# MCU.net
KiCad netlist of a schematic drawn in Altium Designer
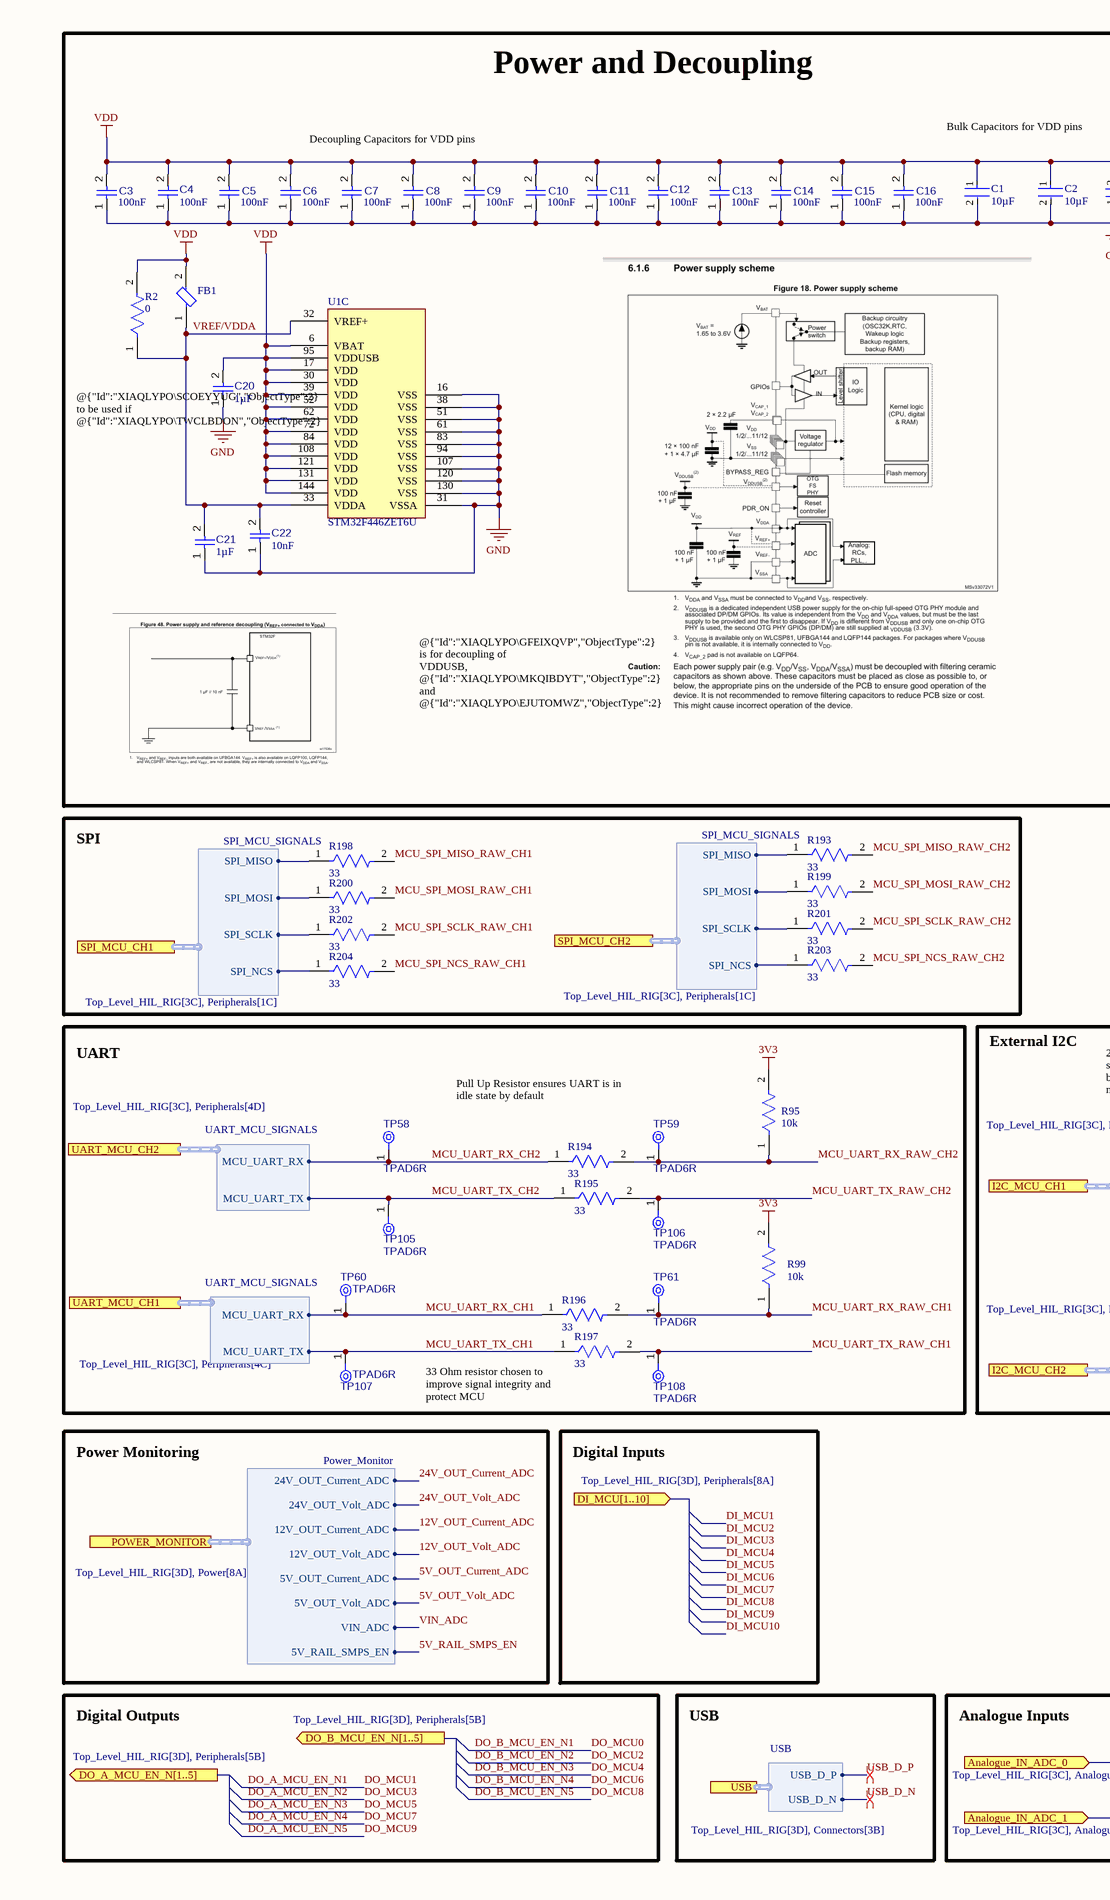
[diagram p0:  MCU.SchDoc, left]
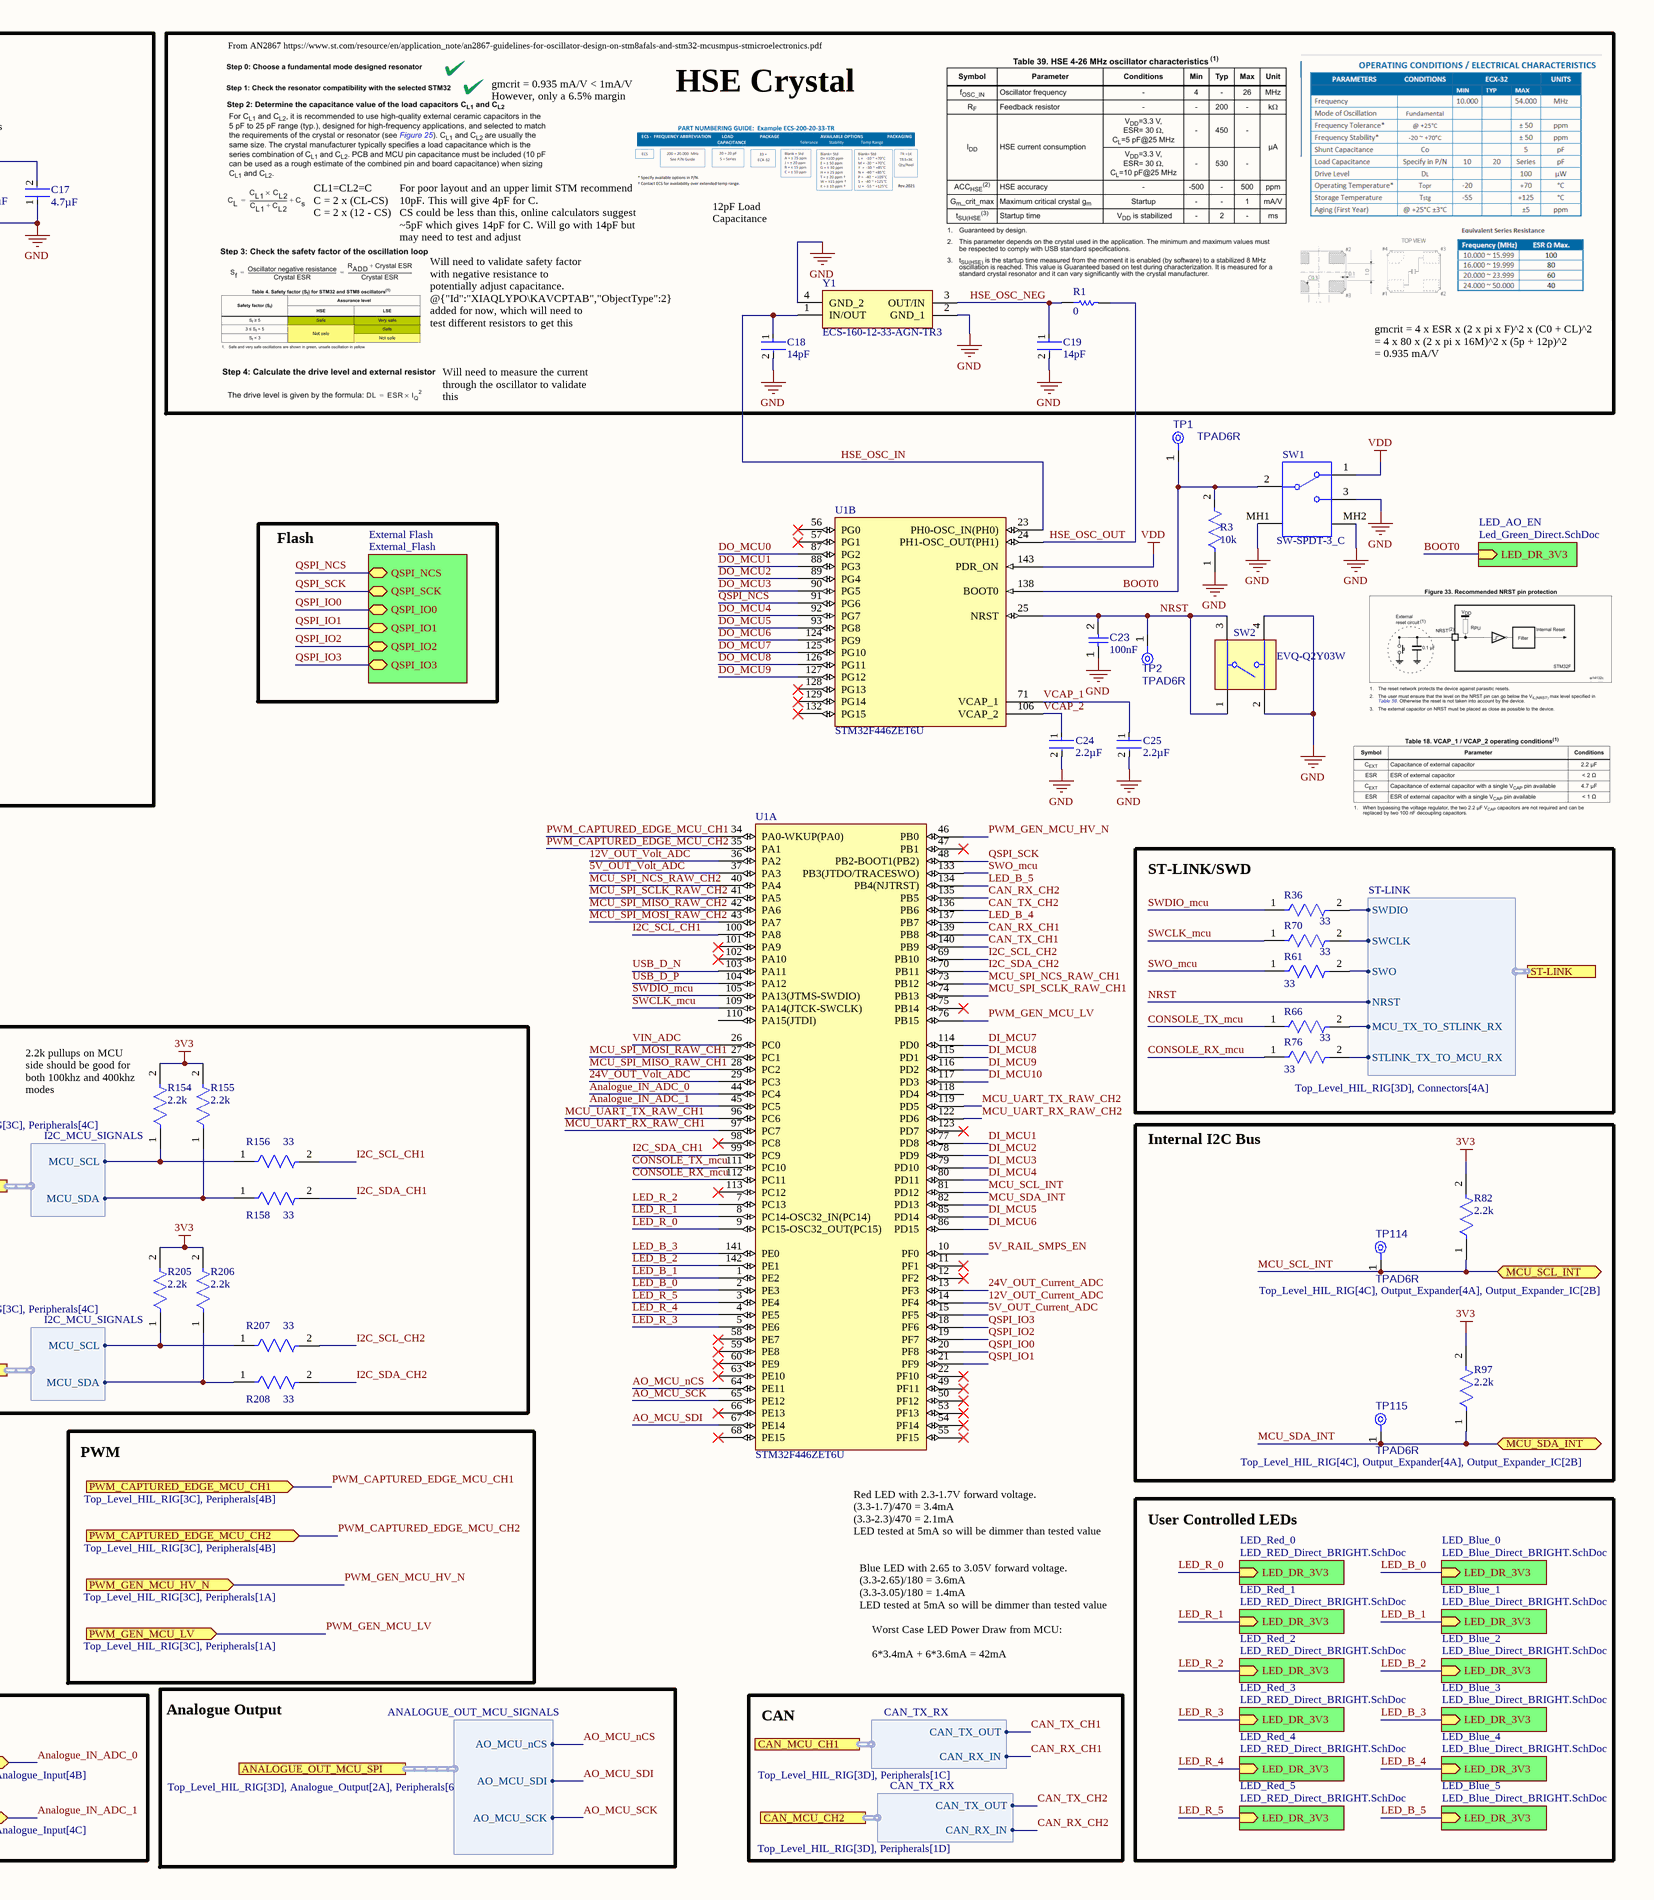
[diagram p1:  MCU.SchDoc, right]

(export (version "E")
  (design (tool "Eeschema 10.0.6"))
  (components
    (comp (ref "C1")
      (value "10µF")
      (footprint "FP-GRM31C-0_2-e0_3_0_8-IPC_C")
      (description "25V 10uF X7R ±10% 1206 Multilayer Ceramic Capacitors MLCC - SMD/SMT ROHS")
      (fields (field (name "TOLERANCE") "10%") (field (name "VOLTAGE") "25V"))
      (libsource (lib "HIL RIG FYP") (part "02cd4be3c70576c341d710602a673aa"))
    )
    (comp (ref "C2")
      (value "10µF")
      (footprint "FP-GRM31C-0_2-e0_3_0_8-IPC_C")
      (description "25V 10uF X7R ±10% 1206 Multilayer Ceramic Capacitors MLCC - SMD/SMT ROHS")
      (fields (field (name "TOLERANCE") "10%") (field (name "VOLTAGE") "25V"))
      (libsource (lib "HIL RIG FYP") (part "02cd4be3c70576c341d710602a673aa"))
    )
    (comp (ref "C3")
      (value "100nF")
      (footprint "CAPC1005X55X25ML05T10")
      (description "10V 100nF X7R ±10% 0402 Multilayer Ceramic Capacitors MLCC - SMD/SMT ROHS")
      (fields (field (name "TOLERANCE") "10%") (field (name "VOLTAGE") "10V"))
      (libsource (lib "HIL RIG FYP") (part "CAP-NP-2"))
    )
    (comp (ref "C4")
      (value "100nF")
      (footprint "CAPC1005X55X25ML05T10")
      (description "10V 100nF X7R ±10% 0402 Multilayer Ceramic Capacitors MLCC - SMD/SMT ROHS")
      (fields (field (name "TOLERANCE") "10%") (field (name "VOLTAGE") "10V"))
      (libsource (lib "HIL RIG FYP") (part "CAP-NP-2"))
    )
    (comp (ref "C5")
      (value "100nF")
      (footprint "CAPC1005X55X25ML05T10")
      (description "10V 100nF X7R ±10% 0402 Multilayer Ceramic Capacitors MLCC - SMD/SMT ROHS")
      (fields (field (name "TOLERANCE") "10%") (field (name "VOLTAGE") "10V"))
      (libsource (lib "HIL RIG FYP") (part "CAP-NP-2"))
    )
    (comp (ref "C6")
      (value "100nF")
      (footprint "CAPC1005X55X25ML05T10")
      (description "10V 100nF X7R ±10% 0402 Multilayer Ceramic Capacitors MLCC - SMD/SMT ROHS")
      (fields (field (name "TOLERANCE") "10%") (field (name "VOLTAGE") "10V"))
      (libsource (lib "HIL RIG FYP") (part "CAP-NP-2"))
    )
    (comp (ref "C7")
      (value "100nF")
      (footprint "CAPC1005X55X25ML05T10")
      (description "10V 100nF X7R ±10% 0402 Multilayer Ceramic Capacitors MLCC - SMD/SMT ROHS")
      (fields (field (name "TOLERANCE") "10%") (field (name "VOLTAGE") "10V"))
      (libsource (lib "HIL RIG FYP") (part "CAP-NP-2"))
    )
    (comp (ref "C8")
      (value "100nF")
      (footprint "CAPC1005X55X25ML05T10")
      (description "10V 100nF X7R ±10% 0402 Multilayer Ceramic Capacitors MLCC - SMD/SMT ROHS")
      (fields (field (name "TOLERANCE") "10%") (field (name "VOLTAGE") "10V"))
      (libsource (lib "HIL RIG FYP") (part "CAP-NP-2"))
    )
    (comp (ref "C9")
      (value "100nF")
      (footprint "CAPC1005X55X25ML05T10")
      (description "10V 100nF X7R ±10% 0402 Multilayer Ceramic Capacitors MLCC - SMD/SMT ROHS")
      (fields (field (name "TOLERANCE") "10%") (field (name "VOLTAGE") "10V"))
      (libsource (lib "HIL RIG FYP") (part "CAP-NP-2"))
    )
    (comp (ref "C10")
      (value "100nF")
      (footprint "CAPC1005X55X25ML05T10")
      (description "10V 100nF X7R ±10% 0402 Multilayer Ceramic Capacitors MLCC - SMD/SMT ROHS")
      (fields (field (name "TOLERANCE") "10%") (field (name "VOLTAGE") "10V"))
      (libsource (lib "HIL RIG FYP") (part "CAP-NP-2"))
    )
    (comp (ref "C11")
      (value "100nF")
      (footprint "CAPC1005X55X25ML05T10")
      (description "10V 100nF X7R ±10% 0402 Multilayer Ceramic Capacitors MLCC - SMD/SMT ROHS")
      (fields (field (name "TOLERANCE") "10%") (field (name "VOLTAGE") "10V"))
      (libsource (lib "HIL RIG FYP") (part "CAP-NP-2"))
    )
    (comp (ref "C12")
      (value "100nF")
      (footprint "CAPC1005X55X25ML05T10")
      (description "10V 100nF X7R ±10% 0402 Multilayer Ceramic Capacitors MLCC - SMD/SMT ROHS")
      (fields (field (name "TOLERANCE") "10%") (field (name "VOLTAGE") "10V"))
      (libsource (lib "HIL RIG FYP") (part "CAP-NP-2"))
    )
    (comp (ref "C13")
      (value "100nF")
      (footprint "CAPC1005X55X25ML05T10")
      (description "10V 100nF X7R ±10% 0402 Multilayer Ceramic Capacitors MLCC - SMD/SMT ROHS")
      (fields (field (name "TOLERANCE") "10%") (field (name "VOLTAGE") "10V"))
      (libsource (lib "HIL RIG FYP") (part "CAP-NP-2"))
    )
    (comp (ref "C14")
      (value "100nF")
      (footprint "CAPC1005X55X25ML05T10")
      (description "10V 100nF X7R ±10% 0402 Multilayer Ceramic Capacitors MLCC - SMD/SMT ROHS")
      (fields (field (name "TOLERANCE") "10%") (field (name "VOLTAGE") "10V"))
      (libsource (lib "HIL RIG FYP") (part "CAP-NP-2"))
    )
    (comp (ref "C15")
      (value "100nF")
      (footprint "CAPC1005X55X25ML05T10")
      (description "10V 100nF X7R ±10% 0402 Multilayer Ceramic Capacitors MLCC - SMD/SMT ROHS")
      (fields (field (name "TOLERANCE") "10%") (field (name "VOLTAGE") "10V"))
      (libsource (lib "HIL RIG FYP") (part "CAP-NP-2"))
    )
    (comp (ref "C16")
      (value "100nF")
      (footprint "CAPC1005X55X25ML05T10")
      (description "10V 100nF X7R ±10% 0402 Multilayer Ceramic Capacitors MLCC - SMD/SMT ROHS")
      (fields (field (name "TOLERANCE") "10%") (field (name "VOLTAGE") "10V"))
      (libsource (lib "HIL RIG FYP") (part "CAP-NP-2"))
    )
    (comp (ref "C17")
      (value "4.7µF")
      (footprint "FP-GRM21B-0_2-e0_2_0_7-MFG")
      (description "50V 4.7uF X7R ±10% 0805 Multilayer Ceramic Capacitors MLCC - SMD/SMT ROHS")
      (fields (field (name "TOLERANCE") "10%") (field (name "Comment") "GRM21BZ71H475KE15L"))
      (libsource (lib "HIL RIG FYP") (part "b4654b650e69147ec39a6b967a45e02"))
    )
    (comp (ref "C18")
      (value "14pF")
      (footprint "FP-GJM155-0_05-IPC_A")
      (description "GJM Series 0402 14 pF 50 V ±1 % Tolerance C0G SMT Monolithic Ceramic Capacitor")
      (fields (field (name "TOLERANCE") "1%") (field (name "Comment") "GJM1555C1H140FB01D"))
      (libsource (lib "HIL RIG FYP") (part "02cd4be3c70576c341d710602a673aa"))
    )
    (comp (ref "C19")
      (value "14pF")
      (footprint "FP-GJM155-0_05-IPC_A")
      (description "GJM Series 0402 14 pF 50 V ±1 % Tolerance C0G SMT Monolithic Ceramic Capacitor")
      (fields (field (name "TOLERANCE") "1%") (field (name "Comment") "GJM1555C1H140FB01D"))
      (libsource (lib "HIL RIG FYP") (part "02cd4be3c70576c341d710602a673aa"))
    )
    (comp (ref "C20")
      (value "1µF")
      (footprint "CAPC1608X90X40LL10T20")
      (description "Chip Capacitor, 1 uF, +/- 10%, 25 V, 0603 (1608 Metric)")
      (fields (field (name "TOLERANCE") "10%") (field (name "Comment") "Capacitor 1 uF +/- 10% 25 V 0603"))
      (libsource (lib "HIL RIG FYP") (part "CAP-NP-2"))
    )
    (comp (ref "C21")
      (value "1µF")
      (footprint "CAPC1608X90X40LL10T20")
      (description "Chip Capacitor, 1 uF, +/- 10%, 25 V, 0603 (1608 Metric)")
      (fields (field (name "TOLERANCE") "10%") (field (name "Comment") "Capacitor 1 uF +/- 10% 25 V 0603"))
      (libsource (lib "HIL RIG FYP") (part "CAP-NP-2"))
    )
    (comp (ref "C22")
      (value "10nF")
      (footprint "CAPC0402(1005)60_L")
      (description "Chip Capacitor, 10nF +/-20%, 50V, 0402, Thickness 0.6 mm")
      (fields (field (name "TOLERANCE") "5%") (field (name "Comment") "Capacitor 10nF +/-20% 50V 0402"))
      (libsource (lib "HIL RIG FYP") (part "CAP-NP-2"))
    )
    (comp (ref "C23")
      (value "100nF")
      (footprint "CAPC1005X55X25ML05T10")
      (description "10V 100nF X7R ±10% 0402 Multilayer Ceramic Capacitors MLCC - SMD/SMT ROHS")
      (fields (field (name "TOLERANCE") "10%") (field (name "VOLTAGE") "10V"))
      (libsource (lib "HIL RIG FYP") (part "CAP-NP-2"))
    )
    (comp (ref "C24")
      (value "2.2µF")
      (footprint "FP-CC0402-IPC_A")
      (description "10V 2.2uF X5R ±10% 0402 Multilayer Ceramic Capacitors MLCC - SMD/SMT ROHS")
      (fields (field (name "TOLERANCE") "10%") (field (name "Comment") "CC0402KRX5R6BB225"))
      (libsource (lib "HIL RIG FYP") (part "11868f565c42a9108669ba33697ecf6"))
    )
    (comp (ref "C25")
      (value "2.2µF")
      (footprint "FP-CC0402-IPC_A")
      (description "10V 2.2uF X5R ±10% 0402 Multilayer Ceramic Capacitors MLCC - SMD/SMT ROHS")
      (fields (field (name "TOLERANCE") "10%") (field (name "Comment") "CC0402KRX5R6BB225"))
      (libsource (lib "HIL RIG FYP") (part "11868f565c42a9108669ba33697ecf6"))
    )
    (comp (ref "FB1")
      (value "BLM15AG121SH1D")
      (footprint "FP-BLM15-0_05-IPC_A")
      (description "Ferrite Beads Multi-Layer 120Ohm 25% 100MHz 500mA 250mOhm DCR 0402 Paper T/R")
      (fields (field (name "TOLERANCE") "25%"))
      (libsource (lib "HIL RIG FYP") (part "5f30dd21d616792df468990f7003faa"))
    )
    (comp (ref "R1")
      (value "0")
      (footprint "RESC1608X55X25ML10T15")
      (description "Chip Resistor, 0 Ohm, 0.1 W, -55 to 155 degC, 0603 (1608 Metric)")
      (fields (field (name "POWER") "100mW") (field (name "TOLERANCE") "5%"))
      (libsource (lib "HIL RIG FYP") (part "RES-2"))
    )
    (comp (ref "R2")
      (value "0")
      (footprint "FP-MCS0402-IPC_B")
      (description "Zero Ohm Resistor, Jumper, 0402 [1005 Metric], Thin Film, 100 mW, 630 mA, Surface Mount Device")
      (fields (field (name "Comment") "MCS04020Z0000ZE000"))
      (libsource (lib "HIL RIG FYP") (part "1029c3af85768c4190bb7ad29bc67b5"))
    )
    (comp (ref "R3")
      (value "10k")
      (footprint "FP-RT0603-IPC_C")
      (description "Res Thin Film 0603 10K Ohm 0.1% 1/10W ¦25ppm/¦C SMD Paper T/R")
      (fields (field (name "TOLERANCE") "0.1%") (field (name "Comment") "RT0603BRD0710KL"))
      (libsource (lib "HIL RIG FYP") (part "1029c3af85768c4190bb7ad29bc67b5"))
    )
    (comp (ref "R36")
      (value "33")
      (footprint "FP-AC0603-IPC_C")
      (description "Res Thick Film 0603 33 Ohm 1% 0.1W(1/10W) ±100ppm/C Pad SMD T/R Automotive AEC-Q200")
      (fields (field (name "TOLERANCE") "1%") (field (name "Comment") "AC0603FR-0733RL"))
      (libsource (lib "HIL RIG FYP") (part "1029c3af85768c4190bb7ad29bc67b5"))
    )
    (comp (ref "R61")
      (value "33")
      (footprint "FP-AC0603-IPC_C")
      (description "Res Thick Film 0603 33 Ohm 1% 0.1W(1/10W) ±100ppm/C Pad SMD T/R Automotive AEC-Q200")
      (fields (field (name "TOLERANCE") "1%") (field (name "Comment") "AC0603FR-0733RL"))
      (libsource (lib "HIL RIG FYP") (part "1029c3af85768c4190bb7ad29bc67b5"))
    )
    (comp (ref "R66")
      (value "33")
      (footprint "FP-AC0603-IPC_C")
      (description "Res Thick Film 0603 33 Ohm 1% 0.1W(1/10W) ±100ppm/C Pad SMD T/R Automotive AEC-Q200")
      (fields (field (name "TOLERANCE") "1%") (field (name "Comment") "AC0603FR-0733RL"))
      (libsource (lib "HIL RIG FYP") (part "1029c3af85768c4190bb7ad29bc67b5"))
    )
    (comp (ref "R70")
      (value "33")
      (footprint "FP-AC0603-IPC_C")
      (description "Res Thick Film 0603 33 Ohm 1% 0.1W(1/10W) ±100ppm/C Pad SMD T/R Automotive AEC-Q200")
      (fields (field (name "TOLERANCE") "1%") (field (name "Comment") "AC0603FR-0733RL"))
      (libsource (lib "HIL RIG FYP") (part "1029c3af85768c4190bb7ad29bc67b5"))
    )
    (comp (ref "R76")
      (value "33")
      (footprint "FP-AC0603-IPC_C")
      (description "Res Thick Film 0603 33 Ohm 1% 0.1W(1/10W) ±100ppm/C Pad SMD T/R Automotive AEC-Q200")
      (fields (field (name "TOLERANCE") "1%") (field (name "Comment") "AC0603FR-0733RL"))
      (libsource (lib "HIL RIG FYP") (part "1029c3af85768c4190bb7ad29bc67b5"))
    )
    (comp (ref "R82")
      (value "2.2k")
      (footprint "FP-RT0603-IPC_C")
      (description "100mW Thin Film Resistor 75V ±25ppm/℃ ±0.1% 2.2kΩ 0603 Chip Resistor - Surface Mount ROHS")
      (fields (field (name "TOLERANCE") "0.1%") (field (name "Comment") "RT0603BRD072K2L"))
      (libsource (lib "HIL RIG FYP") (part "1029c3af85768c4190bb7ad29bc67b5"))
    )
    (comp (ref "R95")
      (value "10k")
      (footprint "FP-RT0603-IPC_C")
      (description "Res Thin Film 0603 10K Ohm 0.1% 1/10W ¦25ppm/¦C SMD Paper T/R")
      (fields (field (name "TOLERANCE") "0.1%") (field (name "Comment") "RT0603BRD0710KL"))
      (libsource (lib "HIL RIG FYP") (part "1029c3af85768c4190bb7ad29bc67b5"))
    )
    (comp (ref "R97")
      (value "2.2k")
      (footprint "FP-RT0603-IPC_C")
      (description "100mW Thin Film Resistor 75V ±25ppm/℃ ±0.1% 2.2kΩ 0603 Chip Resistor - Surface Mount ROHS")
      (fields (field (name "TOLERANCE") "0.1%") (field (name "Comment") "RT0603BRD072K2L"))
      (libsource (lib "HIL RIG FYP") (part "1029c3af85768c4190bb7ad29bc67b5"))
    )
    (comp (ref "R99")
      (value "10k")
      (footprint "FP-RT0603-IPC_C")
      (description "Res Thin Film 0603 10K Ohm 0.1% 1/10W ¦25ppm/¦C SMD Paper T/R")
      (fields (field (name "TOLERANCE") "0.1%") (field (name "Comment") "RT0603BRD0710KL"))
      (libsource (lib "HIL RIG FYP") (part "1029c3af85768c4190bb7ad29bc67b5"))
    )
    (comp (ref "R154")
      (value "2.2k")
      (footprint "FP-RT0603-IPC_C")
      (description "100mW Thin Film Resistor 75V ±25ppm/℃ ±0.1% 2.2kΩ 0603 Chip Resistor - Surface Mount ROHS")
      (fields (field (name "TOLERANCE") "0.1%") (field (name "Comment") "RT0603BRD072K2L"))
      (libsource (lib "HIL RIG FYP") (part "1029c3af85768c4190bb7ad29bc67b5"))
    )
    (comp (ref "R155")
      (value "2.2k")
      (footprint "FP-RT0603-IPC_C")
      (description "100mW Thin Film Resistor 75V ±25ppm/℃ ±0.1% 2.2kΩ 0603 Chip Resistor - Surface Mount ROHS")
      (fields (field (name "TOLERANCE") "0.1%") (field (name "Comment") "RT0603BRD072K2L"))
      (libsource (lib "HIL RIG FYP") (part "1029c3af85768c4190bb7ad29bc67b5"))
    )
    (comp (ref "R156")
      (value "33")
      (footprint "FP-AC0603-IPC_C")
      (description "Res Thick Film 0603 33 Ohm 1% 0.1W(1/10W) ±100ppm/C Pad SMD T/R Automotive AEC-Q200")
      (fields (field (name "TOLERANCE") "1%") (field (name "Comment") "AC0603FR-0733RL"))
      (libsource (lib "HIL RIG FYP") (part "1029c3af85768c4190bb7ad29bc67b5"))
    )
    (comp (ref "R158")
      (value "33")
      (footprint "FP-AC0603-IPC_C")
      (description "Res Thick Film 0603 33 Ohm 1% 0.1W(1/10W) ±100ppm/C Pad SMD T/R Automotive AEC-Q200")
      (fields (field (name "TOLERANCE") "1%") (field (name "Comment") "AC0603FR-0733RL"))
      (libsource (lib "HIL RIG FYP") (part "1029c3af85768c4190bb7ad29bc67b5"))
    )
    (comp (ref "R193")
      (value "33")
      (footprint "FP-AC0603-IPC_C")
      (description "Res Thick Film 0603 33 Ohm 1% 0.1W(1/10W) ±100ppm/C Pad SMD T/R Automotive AEC-Q200")
      (fields (field (name "TOLERANCE") "1%") (field (name "Comment") "AC0603FR-0733RL"))
      (libsource (lib "HIL RIG FYP") (part "1029c3af85768c4190bb7ad29bc67b5"))
    )
    (comp (ref "R194")
      (value "33")
      (footprint "FP-AC0603-IPC_C")
      (description "Res Thick Film 0603 33 Ohm 1% 0.1W(1/10W) ±100ppm/C Pad SMD T/R Automotive AEC-Q200")
      (fields (field (name "TOLERANCE") "1%") (field (name "Comment") "AC0603FR-0733RL"))
      (libsource (lib "HIL RIG FYP") (part "1029c3af85768c4190bb7ad29bc67b5"))
    )
    (comp (ref "R195")
      (value "33")
      (footprint "FP-AC0603-IPC_C")
      (description "Res Thick Film 0603 33 Ohm 1% 0.1W(1/10W) ±100ppm/C Pad SMD T/R Automotive AEC-Q200")
      (fields (field (name "TOLERANCE") "1%") (field (name "Comment") "AC0603FR-0733RL"))
      (libsource (lib "HIL RIG FYP") (part "1029c3af85768c4190bb7ad29bc67b5"))
    )
    (comp (ref "R196")
      (value "33")
      (footprint "FP-AC0603-IPC_C")
      (description "Res Thick Film 0603 33 Ohm 1% 0.1W(1/10W) ±100ppm/C Pad SMD T/R Automotive AEC-Q200")
      (fields (field (name "TOLERANCE") "1%") (field (name "Comment") "AC0603FR-0733RL"))
      (libsource (lib "HIL RIG FYP") (part "1029c3af85768c4190bb7ad29bc67b5"))
    )
    (comp (ref "R197")
      (value "33")
      (footprint "FP-AC0603-IPC_C")
      (description "Res Thick Film 0603 33 Ohm 1% 0.1W(1/10W) ±100ppm/C Pad SMD T/R Automotive AEC-Q200")
      (fields (field (name "TOLERANCE") "1%") (field (name "Comment") "AC0603FR-0733RL"))
      (libsource (lib "HIL RIG FYP") (part "1029c3af85768c4190bb7ad29bc67b5"))
    )
    (comp (ref "R198")
      (value "33")
      (footprint "FP-AC0603-IPC_C")
      (description "Res Thick Film 0603 33 Ohm 1% 0.1W(1/10W) ±100ppm/C Pad SMD T/R Automotive AEC-Q200")
      (fields (field (name "TOLERANCE") "1%") (field (name "Comment") "AC0603FR-0733RL"))
      (libsource (lib "HIL RIG FYP") (part "1029c3af85768c4190bb7ad29bc67b5"))
    )
    (comp (ref "R199")
      (value "33")
      (footprint "FP-AC0603-IPC_C")
      (description "Res Thick Film 0603 33 Ohm 1% 0.1W(1/10W) ±100ppm/C Pad SMD T/R Automotive AEC-Q200")
      (fields (field (name "TOLERANCE") "1%") (field (name "Comment") "AC0603FR-0733RL"))
      (libsource (lib "HIL RIG FYP") (part "1029c3af85768c4190bb7ad29bc67b5"))
    )
    (comp (ref "R200")
      (value "33")
      (footprint "FP-AC0603-IPC_C")
      (description "Res Thick Film 0603 33 Ohm 1% 0.1W(1/10W) ±100ppm/C Pad SMD T/R Automotive AEC-Q200")
      (fields (field (name "TOLERANCE") "1%") (field (name "Comment") "AC0603FR-0733RL"))
      (libsource (lib "HIL RIG FYP") (part "1029c3af85768c4190bb7ad29bc67b5"))
    )
    (comp (ref "R201")
      (value "33")
      (footprint "FP-AC0603-IPC_C")
      (description "Res Thick Film 0603 33 Ohm 1% 0.1W(1/10W) ±100ppm/C Pad SMD T/R Automotive AEC-Q200")
      (fields (field (name "TOLERANCE") "1%") (field (name "Comment") "AC0603FR-0733RL"))
      (libsource (lib "HIL RIG FYP") (part "1029c3af85768c4190bb7ad29bc67b5"))
    )
    (comp (ref "R202")
      (value "33")
      (footprint "FP-AC0603-IPC_C")
      (description "Res Thick Film 0603 33 Ohm 1% 0.1W(1/10W) ±100ppm/C Pad SMD T/R Automotive AEC-Q200")
      (fields (field (name "TOLERANCE") "1%") (field (name "Comment") "AC0603FR-0733RL"))
      (libsource (lib "HIL RIG FYP") (part "1029c3af85768c4190bb7ad29bc67b5"))
    )
    (comp (ref "R203")
      (value "33")
      (footprint "FP-AC0603-IPC_C")
      (description "Res Thick Film 0603 33 Ohm 1% 0.1W(1/10W) ±100ppm/C Pad SMD T/R Automotive AEC-Q200")
      (fields (field (name "TOLERANCE") "1%") (field (name "Comment") "AC0603FR-0733RL"))
      (libsource (lib "HIL RIG FYP") (part "1029c3af85768c4190bb7ad29bc67b5"))
    )
    (comp (ref "R204")
      (value "33")
      (footprint "FP-AC0603-IPC_C")
      (description "Res Thick Film 0603 33 Ohm 1% 0.1W(1/10W) ±100ppm/C Pad SMD T/R Automotive AEC-Q200")
      (fields (field (name "TOLERANCE") "1%") (field (name "Comment") "AC0603FR-0733RL"))
      (libsource (lib "HIL RIG FYP") (part "1029c3af85768c4190bb7ad29bc67b5"))
    )
    (comp (ref "R205")
      (value "2.2k")
      (footprint "FP-RT0603-IPC_C")
      (description "100mW Thin Film Resistor 75V ±25ppm/℃ ±0.1% 2.2kΩ 0603 Chip Resistor - Surface Mount ROHS")
      (fields (field (name "TOLERANCE") "0.1%") (field (name "Comment") "RT0603BRD072K2L"))
      (libsource (lib "HIL RIG FYP") (part "1029c3af85768c4190bb7ad29bc67b5"))
    )
    (comp (ref "R206")
      (value "2.2k")
      (footprint "FP-RT0603-IPC_C")
      (description "100mW Thin Film Resistor 75V ±25ppm/℃ ±0.1% 2.2kΩ 0603 Chip Resistor - Surface Mount ROHS")
      (fields (field (name "TOLERANCE") "0.1%") (field (name "Comment") "RT0603BRD072K2L"))
      (libsource (lib "HIL RIG FYP") (part "1029c3af85768c4190bb7ad29bc67b5"))
    )
    (comp (ref "R207")
      (value "33")
      (footprint "FP-AC0603-IPC_C")
      (description "Res Thick Film 0603 33 Ohm 1% 0.1W(1/10W) ±100ppm/C Pad SMD T/R Automotive AEC-Q200")
      (fields (field (name "TOLERANCE") "1%") (field (name "Comment") "AC0603FR-0733RL"))
      (libsource (lib "HIL RIG FYP") (part "1029c3af85768c4190bb7ad29bc67b5"))
    )
    (comp (ref "R208")
      (value "33")
      (footprint "FP-AC0603-IPC_C")
      (description "Res Thick Film 0603 33 Ohm 1% 0.1W(1/10W) ±100ppm/C Pad SMD T/R Automotive AEC-Q200")
      (fields (field (name "TOLERANCE") "1%") (field (name "Comment") "AC0603FR-0733RL"))
      (libsource (lib "HIL RIG FYP") (part "1029c3af85768c4190bb7ad29bc67b5"))
    )
    (comp (ref "SW1")
      (value "SW-SPDT-3_C")
      (footprint "SS12F44G5")
      (description "Toggle Switches Plugin RoHS")
      (fields (field (name "MANUFACTURER_PART_NUMBER") "SS-12F44-G5"))
      (libsource (lib "HIL RIG FYP") (part "SW-SPDT-3_C"))
    )
    (comp (ref "SW2")
      (value "EVQ-Q2Y03W")
      (footprint "PNSC-EVQQ2_V")
      (description "Switch Tactile ON OFF SPST Round Button J-Bend 0.02A 15VDC 3.5N SMD Embossed T/R")
      (libsource (lib "HIL RIG FYP") (part "SW-SPST-4"))
    )
    (comp (ref "TP1")
      (value "TPAD6R")
      (footprint "TP06R")
      (description "0.6mm round")
      (libsource (lib "HIL RIG FYP") (part "CMP-001-0001-4"))
    )
    (comp (ref "TP2")
      (value "TPAD6R")
      (footprint "TP06R")
      (description "0.6mm round")
      (libsource (lib "HIL RIG FYP") (part "CMP-001-0001-4"))
    )
    (comp (ref "TP58")
      (value "TPAD6R")
      (footprint "TP06R")
      (description "0.6mm round")
      (libsource (lib "HIL RIG FYP") (part "CMP-001-0001-4"))
    )
    (comp (ref "TP59")
      (value "TPAD6R")
      (footprint "TP06R")
      (description "0.6mm round")
      (libsource (lib "HIL RIG FYP") (part "CMP-001-0001-4"))
    )
    (comp (ref "TP60")
      (value "TPAD6R")
      (footprint "TP06R")
      (description "0.6mm round")
      (libsource (lib "HIL RIG FYP") (part "CMP-001-0001-4"))
    )
    (comp (ref "TP61")
      (value "TPAD6R")
      (footprint "TP06R")
      (description "0.6mm round")
      (libsource (lib "HIL RIG FYP") (part "CMP-001-0001-4"))
    )
    (comp (ref "TP105")
      (value "TPAD6R")
      (footprint "TP06R")
      (description "0.6mm round")
      (libsource (lib "HIL RIG FYP") (part "CMP-001-0001-4"))
    )
    (comp (ref "TP106")
      (value "TPAD6R")
      (footprint "TP06R")
      (description "0.6mm round")
      (libsource (lib "HIL RIG FYP") (part "CMP-001-0001-4"))
    )
    (comp (ref "TP107")
      (value "TPAD6R")
      (footprint "TP06R")
      (description "0.6mm round")
      (libsource (lib "HIL RIG FYP") (part "CMP-001-0001-4"))
    )
    (comp (ref "TP108")
      (value "TPAD6R")
      (footprint "TP06R")
      (description "0.6mm round")
      (libsource (lib "HIL RIG FYP") (part "CMP-001-0001-4"))
    )
    (comp (ref "TP114")
      (value "TPAD6R")
      (footprint "TP06R")
      (description "0.6mm round")
      (libsource (lib "HIL RIG FYP") (part "CMP-001-0001-4"))
    )
    (comp (ref "TP115")
      (value "TPAD6R")
      (footprint "TP06R")
      (description "0.6mm round")
      (libsource (lib "HIL RIG FYP") (part "CMP-001-0001-4"))
    )
    (comp (ref "U1")
      (value "STM32F446ZET6U")
      (footprint "STM-LQFP144_N")
      (description "Mcu, 32 Bit, CORTEX-M4, 180MHZ, LQFP-144")
      (libsource (lib "HIL RIG FYP") (part "MC-ARM-STM32F446-LQFP144"))
    )
    (comp (ref "Y1")
      (value "ECS-160-12-33-AGN-TR3")
      (footprint "ECS1601233AGNTR3")
      (description "Crystal or Oscillator")
      (fields (field (name "MOUSER PART NUMBER") "520-160-12-33AGN-TR3"))
      (libsource (lib "HIL RIG FYP") (part "ECS-160-12-33-AGN-TR3"))
    )
  )
  (nets
    (net (code "9") (name "/5V_OUT_Current_ADC") (class "Default")
      (node (ref "U1") (pin "15") (pinfunction "PF5_15") (pintype "bidirectional"))
    )
    (net (code "10") (name "/5V_OUT_Volt_ADC") (class "Default")
      (node (ref "U1") (pin "37") (pinfunction "PA3_37") (pintype "bidirectional"))
    )
    (net (code "11") (name "/5V_RAIL_SMPS_EN") (class "Default")
      (node (ref "U1") (pin "10") (pinfunction "PF0_10") (pintype "bidirectional"))
    )
    (net (code "12") (name "/12V_OUT_Current_ADC") (class "Default")
      (node (ref "U1") (pin "14") (pinfunction "PF4_14") (pintype "bidirectional"))
    )
    (net (code "13") (name "/12V_OUT_Volt_ADC") (class "Default")
      (node (ref "U1") (pin "36") (pinfunction "PA2_36") (pintype "bidirectional"))
    )
    (net (code "14") (name "/24V_OUT_Current_ADC") (class "Default")
      (node (ref "U1") (pin "13") (pinfunction "PF3_13") (pintype "bidirectional"))
    )
    (net (code "15") (name "/24V_OUT_Volt_ADC") (class "Default")
      (node (ref "U1") (pin "29") (pinfunction "PC3_29") (pintype "bidirectional"))
    )
    (net (code "16") (name "/AO_MCU_SCK") (class "Default")
      (node (ref "U1") (pin "65") (pinfunction "PE12_65") (pintype "bidirectional"))
    )
    (net (code "17") (name "/AO_MCU_SDI") (class "Default")
      (node (ref "U1") (pin "67") (pinfunction "PE14_67") (pintype "bidirectional"))
    )
    (net (code "18") (name "/AO_MCU_nCS") (class "Default")
      (node (ref "U1") (pin "64") (pinfunction "PE11_64") (pintype "bidirectional"))
    )
    (net (code "19") (name "/Analogue_IN_ADC_0") (class "Default")
      (node (ref "U1") (pin "44") (pinfunction "PC4_44") (pintype "bidirectional"))
    )
    (net (code "20") (name "/Analogue_IN_ADC_1") (class "Default")
      (node (ref "U1") (pin "45") (pinfunction "PC5_45") (pintype "bidirectional"))
    )
    (net (code "21") (name "/BOOT0") (class "Default")
      (node (ref "R3") (pin "2") (pinfunction "2_2") (pintype "passive"))
      (node (ref "SW1") (pin "2") (pinfunction "2_2") (pintype "passive"))
      (node (ref "TP1") (pin "1") (pinfunction "TP_1") (pintype "passive"))
      (node (ref "U1") (pin "138") (pinfunction "BOOT0_138") (pintype "input"))
    )
    (net (code "22") (name "/CAN_RX_CH1") (class "Default")
      (node (ref "U1") (pin "139") (pinfunction "PB8_139") (pintype "bidirectional"))
    )
    (net (code "23") (name "/CAN_RX_CH2") (class "Default")
      (node (ref "U1") (pin "135") (pinfunction "PB5_135") (pintype "bidirectional"))
    )
    (net (code "24") (name "/CAN_TX_CH1") (class "Default")
      (node (ref "U1") (pin "140") (pinfunction "PB9_140") (pintype "bidirectional"))
    )
    (net (code "25") (name "/CAN_TX_CH2") (class "Default")
      (node (ref "U1") (pin "136") (pinfunction "PB6_136") (pintype "bidirectional"))
    )
    (net (code "26") (name "/CONSOLE_RX_mcu") (class "Default")
      (node (ref "R76") (pin "1") (pinfunction "1_1") (pintype "passive"))
      (node (ref "U1") (pin "112") (pinfunction "PC11_112") (pintype "bidirectional"))
    )
    (net (code "27") (name "/CONSOLE_TX_mcu") (class "Default")
      (node (ref "R66") (pin "1") (pinfunction "1_1") (pintype "passive"))
      (node (ref "U1") (pin "111") (pinfunction "PC10_111") (pintype "bidirectional"))
    )
    (net (code "28") (name "/DI_MCU1") (class "Default")
      (node (ref "U1") (pin "77") (pinfunction "PD8_77") (pintype "bidirectional"))
    )
    (net (code "29") (name "/DI_MCU2") (class "Default")
      (node (ref "U1") (pin "78") (pinfunction "PD9_78") (pintype "bidirectional"))
    )
    (net (code "30") (name "/DI_MCU3") (class "Default")
      (node (ref "U1") (pin "79") (pinfunction "PD10_79") (pintype "bidirectional"))
    )
    (net (code "31") (name "/DI_MCU4") (class "Default")
      (node (ref "U1") (pin "80") (pinfunction "PD11_80") (pintype "bidirectional"))
    )
    (net (code "32") (name "/DI_MCU5") (class "Default")
      (node (ref "U1") (pin "85") (pinfunction "PD14_85") (pintype "bidirectional"))
    )
    (net (code "33") (name "/DI_MCU6") (class "Default")
      (node (ref "U1") (pin "86") (pinfunction "PD15_86") (pintype "bidirectional"))
    )
    (net (code "34") (name "/DI_MCU7") (class "Default")
      (node (ref "U1") (pin "114") (pinfunction "PD0_114") (pintype "bidirectional"))
    )
    (net (code "35") (name "/DI_MCU8") (class "Default")
      (node (ref "U1") (pin "115") (pinfunction "PD1_115") (pintype "bidirectional"))
    )
    (net (code "36") (name "/DI_MCU9") (class "Default")
      (node (ref "U1") (pin "116") (pinfunction "PD2_116") (pintype "bidirectional"))
    )
    (net (code "37") (name "/DI_MCU10") (class "Default")
      (node (ref "U1") (pin "117") (pinfunction "PD3_117") (pintype "bidirectional"))
    )
    (net (code "39") (name "/DO_A_MCU_EN_N1") (class "Default")
      (node (ref "U1") (pin "88") (pinfunction "PG3_88") (pintype "bidirectional"))
    )
    (net (code "40") (name "/DO_A_MCU_EN_N2") (class "Default")
      (node (ref "U1") (pin "90") (pinfunction "PG5_90") (pintype "bidirectional"))
    )
    (net (code "41") (name "/DO_A_MCU_EN_N3") (class "Default")
      (node (ref "U1") (pin "93") (pinfunction "PG8_93") (pintype "bidirectional"))
    )
    (net (code "42") (name "/DO_A_MCU_EN_N4") (class "Default")
      (node (ref "U1") (pin "125") (pinfunction "PG10_125") (pintype "bidirectional"))
    )
    (net (code "43") (name "/DO_A_MCU_EN_N5") (class "Default")
      (node (ref "U1") (pin "127") (pinfunction "PG12_127") (pintype "bidirectional"))
    )
    (net (code "45") (name "/DO_B_MCU_EN_N1") (class "Default")
      (node (ref "U1") (pin "87") (pinfunction "PG2_87") (pintype "bidirectional"))
    )
    (net (code "46") (name "/DO_B_MCU_EN_N2") (class "Default")
      (node (ref "U1") (pin "89") (pinfunction "PG4_89") (pintype "bidirectional"))
    )
    (net (code "47") (name "/DO_B_MCU_EN_N3") (class "Default")
      (node (ref "U1") (pin "92") (pinfunction "PG7_92") (pintype "bidirectional"))
    )
    (net (code "48") (name "/DO_B_MCU_EN_N4") (class "Default")
      (node (ref "U1") (pin "124") (pinfunction "PG9_124") (pintype "bidirectional"))
    )
    (net (code "49") (name "/DO_B_MCU_EN_N5") (class "Default")
      (node (ref "U1") (pin "126") (pinfunction "PG11_126") (pintype "bidirectional"))
    )
    (net (code "51") (name "/HSE_OSC_IN") (class "Default")
      (node (ref "C18") (pin "1") (pinfunction "1_1") (pintype "passive"))
      (node (ref "U1") (pin "23") (pinfunction "PH0-OSC_IN(PH0)_23") (pintype "bidirectional"))
      (node (ref "Y1") (pin "1") (pinfunction "IN/OUT_1") (pintype "passive"))
    )
    (net (code "52") (name "/HSE_OSC_NEG") (class "Default")
      (node (ref "C19") (pin "1") (pinfunction "1_1") (pintype "passive"))
      (node (ref "R1") (pin "1") (pinfunction "1_1") (pintype "passive"))
      (node (ref "Y1") (pin "3") (pinfunction "OUT/IN_3") (pintype "passive"))
    )
    (net (code "53") (name "/HSE_OSC_OUT") (class "Default")
      (node (ref "R1") (pin "2") (pinfunction "2_2") (pintype "passive"))
      (node (ref "U1") (pin "24") (pinfunction "PH1-OSC_OUT(PH1)_24") (pintype "bidirectional"))
    )
    (net (code "54") (name "/I2C_SCL_CH1") (class "Default")
      (node (ref "R156") (pin "2") (pinfunction "2_2") (pintype "passive"))
      (node (ref "U1") (pin "100") (pinfunction "PA8_100") (pintype "bidirectional"))
    )
    (net (code "55") (name "/I2C_SCL_CH2") (class "Default")
      (node (ref "R207") (pin "2") (pinfunction "2_2") (pintype "passive"))
      (node (ref "U1") (pin "69") (pinfunction "PB10_69") (pintype "bidirectional"))
    )
    (net (code "56") (name "/I2C_SDA_CH1") (class "Default")
      (node (ref "R158") (pin "2") (pinfunction "2_2") (pintype "passive"))
      (node (ref "U1") (pin "99") (pinfunction "PC9_99") (pintype "bidirectional"))
    )
    (net (code "57") (name "/I2C_SDA_CH2") (class "Default")
      (node (ref "R208") (pin "2") (pinfunction "2_2") (pintype "passive"))
      (node (ref "U1") (pin "70") (pinfunction "PB11_70") (pintype "bidirectional"))
    )
    (net (code "58") (name "/LED_B_0") (class "Default")
      (node (ref "U1") (pin "2") (pinfunction "PE3_2") (pintype "bidirectional"))
    )
    (net (code "59") (name "/LED_B_1") (class "Default")
      (node (ref "U1") (pin "1") (pinfunction "PE2_1") (pintype "bidirectional"))
    )
    (net (code "60") (name "/LED_B_2") (class "Default")
      (node (ref "U1") (pin "142") (pinfunction "PE1_142") (pintype "bidirectional"))
    )
    (net (code "61") (name "/LED_B_3") (class "Default")
      (node (ref "U1") (pin "141") (pinfunction "PE0_141") (pintype "bidirectional"))
    )
    (net (code "62") (name "/LED_B_4") (class "Default")
      (node (ref "U1") (pin "137") (pinfunction "PB7_137") (pintype "bidirectional"))
    )
    (net (code "63") (name "/LED_B_5") (class "Default")
      (node (ref "U1") (pin "134") (pinfunction "PB4(NJTRST)_134") (pintype "bidirectional"))
    )
    (net (code "64") (name "/LED_R_0") (class "Default")
      (node (ref "U1") (pin "9") (pinfunction "PC15-OSC32_OUT(PC15)_9") (pintype "bidirectional"))
    )
    (net (code "65") (name "/LED_R_1") (class "Default")
      (node (ref "U1") (pin "8") (pinfunction "PC14-OSC32_IN(PC14)_8") (pintype "bidirectional"))
    )
    (net (code "66") (name "/LED_R_2") (class "Default")
      (node (ref "U1") (pin "7") (pinfunction "PC13_7") (pintype "bidirectional"))
    )
    (net (code "67") (name "/LED_R_3") (class "Default")
      (node (ref "U1") (pin "5") (pinfunction "PE6_5") (pintype "bidirectional"))
    )
    (net (code "68") (name "/LED_R_4") (class "Default")
      (node (ref "U1") (pin "4") (pinfunction "PE5_4") (pintype "bidirectional"))
    )
    (net (code "69") (name "/LED_R_5") (class "Default")
      (node (ref "U1") (pin "3") (pinfunction "PE4_3") (pintype "bidirectional"))
    )
    (net (code "70") (name "/MCU_SCL_INT") (class "Default")
      (node (ref "R82") (pin "1") (pinfunction "1_1") (pintype "passive"))
      (node (ref "TP114") (pin "1") (pinfunction "TP_1") (pintype "passive"))
      (node (ref "U1") (pin "81") (pinfunction "PD12_81") (pintype "bidirectional"))
    )
    (net (code "71") (name "/MCU_SDA_INT") (class "Default")
      (node (ref "R97") (pin "1") (pinfunction "1_1") (pintype "passive"))
      (node (ref "TP115") (pin "1") (pinfunction "TP_1") (pintype "passive"))
      (node (ref "U1") (pin "82") (pinfunction "PD13_82") (pintype "bidirectional"))
    )
    (net (code "72") (name "/MCU_SPI_MISO_RAW_CH1") (class "Default")
      (node (ref "R198") (pin "2") (pinfunction "2_2") (pintype "passive"))
      (node (ref "U1") (pin "28") (pinfunction "PC2_28") (pintype "bidirectional"))
    )
    (net (code "73") (name "/MCU_SPI_MISO_RAW_CH2") (class "Default")
      (node (ref "R193") (pin "2") (pinfunction "2_2") (pintype "passive"))
      (node (ref "U1") (pin "42") (pinfunction "PA6_42") (pintype "bidirectional"))
    )
    (net (code "74") (name "/MCU_SPI_MOSI_RAW_CH1") (class "Default")
      (node (ref "R200") (pin "2") (pinfunction "2_2") (pintype "passive"))
      (node (ref "U1") (pin "27") (pinfunction "PC1_27") (pintype "bidirectional"))
    )
    (net (code "75") (name "/MCU_SPI_MOSI_RAW_CH2") (class "Default")
      (node (ref "R199") (pin "2") (pinfunction "2_2") (pintype "passive"))
      (node (ref "U1") (pin "43") (pinfunction "PA7_43") (pintype "bidirectional"))
    )
    (net (code "76") (name "/MCU_SPI_NCS_RAW_CH1") (class "Default")
      (node (ref "R204") (pin "2") (pinfunction "2_2") (pintype "passive"))
      (node (ref "U1") (pin "73") (pinfunction "PB12_73") (pintype "bidirectional"))
    )
    (net (code "77") (name "/MCU_SPI_NCS_RAW_CH2") (class "Default")
      (node (ref "R203") (pin "2") (pinfunction "2_2") (pintype "passive"))
      (node (ref "U1") (pin "40") (pinfunction "PA4_40") (pintype "bidirectional"))
    )
    (net (code "78") (name "/MCU_SPI_SCLK_RAW_CH1") (class "Default")
      (node (ref "R202") (pin "2") (pinfunction "2_2") (pintype "passive"))
      (node (ref "U1") (pin "74") (pinfunction "PB13_74") (pintype "bidirectional"))
    )
    (net (code "79") (name "/MCU_SPI_SCLK_RAW_CH2") (class "Default")
      (node (ref "R201") (pin "2") (pinfunction "2_2") (pintype "passive"))
      (node (ref "U1") (pin "41") (pinfunction "PA5_41") (pintype "bidirectional"))
    )
    (net (code "80") (name "/MCU_TX_TO_STLINK_RX") (class "Default")
      (node (ref "R66") (pin "2") (pinfunction "2_2") (pintype "passive"))
    )
    (net (code "81") (name "/MCU_UART_RX_CH1") (class "Default")
      (node (ref "R196") (pin "1") (pinfunction "1_1") (pintype "passive"))
      (node (ref "TP60") (pin "1") (pinfunction "TP_1") (pintype "passive"))
    )
    (net (code "82") (name "/MCU_UART_RX_CH2") (class "Default")
      (node (ref "R194") (pin "1") (pinfunction "1_1") (pintype "passive"))
      (node (ref "TP58") (pin "1") (pinfunction "TP_1") (pintype "passive"))
    )
    (net (code "83") (name "/MCU_UART_RX_RAW_CH1") (class "Default")
      (node (ref "R196") (pin "2") (pinfunction "2_2") (pintype "passive"))
      (node (ref "R99") (pin "1") (pinfunction "1_1") (pintype "passive"))
      (node (ref "TP61") (pin "1") (pinfunction "TP_1") (pintype "passive"))
      (node (ref "U1") (pin "97") (pinfunction "PC7_97") (pintype "bidirectional"))
    )
    (net (code "84") (name "/MCU_UART_RX_RAW_CH2") (class "Default")
      (node (ref "R194") (pin "2") (pinfunction "2_2") (pintype "passive"))
      (node (ref "R95") (pin "1") (pinfunction "1_1") (pintype "passive"))
      (node (ref "TP59") (pin "1") (pinfunction "TP_1") (pintype "passive"))
      (node (ref "U1") (pin "122") (pinfunction "PD6_122") (pintype "bidirectional"))
    )
    (net (code "85") (name "/MCU_UART_TX_CH1") (class "Default")
      (node (ref "R197") (pin "1") (pinfunction "1_1") (pintype "passive"))
      (node (ref "TP107") (pin "1") (pinfunction "TP_1") (pintype "passive"))
    )
    (net (code "86") (name "/MCU_UART_TX_CH2") (class "Default")
      (node (ref "R195") (pin "1") (pinfunction "1_1") (pintype "passive"))
      (node (ref "TP105") (pin "1") (pinfunction "TP_1") (pintype "passive"))
    )
    (net (code "87") (name "/MCU_UART_TX_RAW_CH1") (class "Default")
      (node (ref "R197") (pin "2") (pinfunction "2_2") (pintype "passive"))
      (node (ref "TP108") (pin "1") (pinfunction "TP_1") (pintype "passive"))
      (node (ref "U1") (pin "96") (pinfunction "PC6_96") (pintype "bidirectional"))
    )
    (net (code "88") (name "/MCU_UART_TX_RAW_CH2") (class "Default")
      (node (ref "R195") (pin "2") (pinfunction "2_2") (pintype "passive"))
      (node (ref "TP106") (pin "1") (pinfunction "TP_1") (pintype "passive"))
      (node (ref "U1") (pin "119") (pinfunction "PD5_119") (pintype "bidirectional"))
    )
    (net (code "89") (name "/NRST") (class "Default")
      (node (ref "C23") (pin "2") (pinfunction "2_2") (pintype "passive"))
      (node (ref "SW2") (pin "1") (pinfunction "A_1") (pintype "passive"))
      (node (ref "SW2") (pin "3") (pinfunction "A'_3") (pintype "passive"))
      (node (ref "TP2") (pin "1") (pinfunction "TP_1") (pintype "passive"))
      (node (ref "U1") (pin "25") (pinfunction "NRST_25") (pintype "bidirectional"))
    )
    (net (code "90") (name "/PWM_CAPTURED_EDGE_MCU_CH1") (class "Default")
      (node (ref "U1") (pin "34") (pinfunction "PA0-WKUP(PA0)_34") (pintype "bidirectional"))
    )
    (net (code "91") (name "/PWM_CAPTURED_EDGE_MCU_CH2") (class "Default")
      (node (ref "U1") (pin "35") (pinfunction "PA1_35") (pintype "bidirectional"))
    )
    (net (code "92") (name "/PWM_GEN_MCU_HV_N") (class "Default")
      (node (ref "U1") (pin "46") (pinfunction "PB0_46") (pintype "bidirectional"))
    )
    (net (code "93") (name "/PWM_GEN_MCU_LV") (class "Default")
      (node (ref "U1") (pin "76") (pinfunction "PB15_76") (pintype "bidirectional"))
    )
    (net (code "94") (name "/QSPI_IO0") (class "Default")
      (node (ref "U1") (pin "20") (pinfunction "PF8_20") (pintype "bidirectional"))
    )
    (net (code "95") (name "/QSPI_IO1") (class "Default")
      (node (ref "U1") (pin "21") (pinfunction "PF9_21") (pintype "bidirectional"))
    )
    (net (code "96") (name "/QSPI_IO2") (class "Default")
      (node (ref "U1") (pin "19") (pinfunction "PF7_19") (pintype "bidirectional"))
    )
    (net (code "97") (name "/QSPI_IO3") (class "Default")
      (node (ref "U1") (pin "18") (pinfunction "PF6_18") (pintype "bidirectional"))
    )
    (net (code "98") (name "/QSPI_NCS") (class "Default")
      (node (ref "U1") (pin "91") (pinfunction "PG6_91") (pintype "bidirectional"))
    )
    (net (code "99") (name "/QSPI_SCK") (class "Default")
      (node (ref "U1") (pin "48") (pinfunction "PB2-BOOT1(PB2)_48") (pintype "bidirectional"))
    )
    (net (code "100") (name "/STLINK_TX_TO_MCU_RX") (class "Default")
      (node (ref "R76") (pin "2") (pinfunction "2_2") (pintype "passive"))
    )
    (net (code "101") (name "/SWCLK") (class "Default")
      (node (ref "R70") (pin "2") (pinfunction "2_2") (pintype "passive"))
    )
    (net (code "102") (name "/SWCLK_mcu") (class "Default")
      (node (ref "R70") (pin "1") (pinfunction "1_1") (pintype "passive"))
      (node (ref "U1") (pin "109") (pinfunction "PA14(JTCK-SWCLK)_109") (pintype "bidirectional"))
    )
    (net (code "103") (name "/SWDIO") (class "Default")
      (node (ref "R36") (pin "2") (pinfunction "2_2") (pintype "passive"))
    )
    (net (code "104") (name "/SWDIO_mcu") (class "Default")
      (node (ref "R36") (pin "1") (pinfunction "1_1") (pintype "passive"))
      (node (ref "U1") (pin "105") (pinfunction "PA13(JTMS-SWDIO)_105") (pintype "bidirectional"))
    )
    (net (code "105") (name "/SWO") (class "Default")
      (node (ref "R61") (pin "2") (pinfunction "2_2") (pintype "passive"))
    )
    (net (code "106") (name "/SWO_mcu") (class "Default")
      (node (ref "R61") (pin "1") (pinfunction "1_1") (pintype "passive"))
      (node (ref "U1") (pin "133") (pinfunction "PB3(JTDO/TRACESWO)_133") (pintype "bidirectional"))
    )
    (net (code "107") (name "/USB_D_N") (class "Default")
      (node (ref "U1") (pin "103") (pinfunction "PA11_103") (pintype "bidirectional"))
    )
    (net (code "108") (name "/USB_D_P") (class "Default")
      (node (ref "U1") (pin "104") (pinfunction "PA12_104") (pintype "bidirectional"))
    )
    (net (code "109") (name "/VCAP_1") (class "Default")
      (node (ref "C25") (pin "1") (pinfunction "1_1") (pintype "passive"))
      (node (ref "U1") (pin "71") (pinfunction "VCAP_1_71") (pintype "passive"))
    )
    (net (code "110") (name "/VCAP_2") (class "Default")
      (node (ref "C24") (pin "1") (pinfunction "1_1") (pintype "passive"))
      (node (ref "U1") (pin "106") (pinfunction "VCAP_2_106") (pintype "passive"))
    )
    (net (code "111") (name "/VIN_ADC") (class "Default")
      (node (ref "U1") (pin "26") (pinfunction "PC0_26") (pintype "bidirectional"))
    )
    (net (code "112") (name "/VREF{slash}VDDA") (class "Default")
      (node (ref "C21") (pin "2") (pinfunction "2_2") (pintype "passive"))
      (node (ref "C22") (pin "2") (pinfunction "2_2") (pintype "passive"))
      (node (ref "FB1") (pin "1") (pinfunction "1_1") (pintype "passive"))
      (node (ref "R2") (pin "1") (pinfunction "1_1") (pintype "passive"))
      (node (ref "U1") (pin "32") (pinfunction "VREF+_32") (pintype "power_in"))
      (node (ref "U1") (pin "33") (pinfunction "VDDA_33") (pintype "power_in"))
    )
    (net (code "121") (name "3V3") (class "Default")
      (node (ref "R154") (pin "2") (pinfunction "2_2") (pintype "passive"))
      (node (ref "R155") (pin "2") (pinfunction "2_2") (pintype "passive"))
      (node (ref "R205") (pin "2") (pinfunction "2_2") (pintype "passive"))
      (node (ref "R206") (pin "2") (pinfunction "2_2") (pintype "passive"))
      (node (ref "R82") (pin "2") (pinfunction "2_2") (pintype "passive"))
      (node (ref "R95") (pin "2") (pinfunction "2_2") (pintype "passive"))
      (node (ref "R97") (pin "2") (pinfunction "2_2") (pintype "passive"))
      (node (ref "R99") (pin "2") (pinfunction "2_2") (pintype "passive"))
    )
    (net (code "122") (name "GND") (class "Default")
      (node (ref "C1") (pin "2") (pinfunction "2_2") (pintype "passive"))
      (node (ref "C10") (pin "1") (pinfunction "1_1") (pintype "passive"))
      (node (ref "C11") (pin "1") (pinfunction "1_1") (pintype "passive"))
      (node (ref "C12") (pin "1") (pinfunction "1_1") (pintype "passive"))
      (node (ref "C13") (pin "1") (pinfunction "1_1") (pintype "passive"))
      (node (ref "C14") (pin "1") (pinfunction "1_1") (pintype "passive"))
      (node (ref "C15") (pin "1") (pinfunction "1_1") (pintype "passive"))
      (node (ref "C16") (pin "1") (pinfunction "1_1") (pintype "passive"))
      (node (ref "C17") (pin "1") (pinfunction "1_1") (pintype "passive"))
      (node (ref "C18") (pin "2") (pinfunction "2_2") (pintype "passive"))
      (node (ref "C19") (pin "2") (pinfunction "2_2") (pintype "passive"))
      (node (ref "C2") (pin "2") (pinfunction "2_2") (pintype "passive"))
      (node (ref "C20") (pin "1") (pinfunction "1_1") (pintype "passive"))
      (node (ref "C21") (pin "1") (pinfunction "1_1") (pintype "passive"))
      (node (ref "C22") (pin "1") (pinfunction "1_1") (pintype "passive"))
      (node (ref "C23") (pin "1") (pinfunction "1_1") (pintype "passive"))
      (node (ref "C24") (pin "2") (pinfunction "2_2") (pintype "passive"))
      (node (ref "C25") (pin "2") (pinfunction "2_2") (pintype "passive"))
      (node (ref "C3") (pin "1") (pinfunction "1_1") (pintype "passive"))
      (node (ref "C4") (pin "1") (pinfunction "1_1") (pintype "passive"))
      (node (ref "C5") (pin "1") (pinfunction "1_1") (pintype "passive"))
      (node (ref "C6") (pin "1") (pinfunction "1_1") (pintype "passive"))
      (node (ref "C7") (pin "1") (pinfunction "1_1") (pintype "passive"))
      (node (ref "C8") (pin "1") (pinfunction "1_1") (pintype "passive"))
      (node (ref "C9") (pin "1") (pinfunction "1_1") (pintype "passive"))
      (node (ref "R3") (pin "1") (pinfunction "1_1") (pintype "passive"))
      (node (ref "SW1") (pin "3") (pinfunction "3_3") (pintype "passive"))
      (node (ref "SW1") (pin "MH1") (pinfunction "MH1_MH1") (pintype "passive"))
      (node (ref "SW1") (pin "MH2") (pinfunction "MH2_MH2") (pintype "passive"))
      (node (ref "SW2") (pin "2") (pinfunction "B_2") (pintype "passive"))
      (node (ref "SW2") (pin "4") (pinfunction "B'_4") (pintype "passive"))
      (node (ref "U1") (pin "107") (pinfunction "VSS_107") (pintype "power_in"))
      (node (ref "U1") (pin "120") (pinfunction "VSS_120") (pintype "power_in"))
      (node (ref "U1") (pin "130") (pinfunction "VSS_130") (pintype "power_in"))
      (node (ref "U1") (pin "16") (pinfunction "VSS_16") (pintype "power_in"))
      (node (ref "U1") (pin "31") (pinfunction "VSSA_31") (pintype "power_in"))
      (node (ref "U1") (pin "38") (pinfunction "VSS_38") (pintype "power_in"))
      (node (ref "U1") (pin "51") (pinfunction "VSS_51") (pintype "power_in"))
      (node (ref "U1") (pin "61") (pinfunction "VSS_61") (pintype "power_in"))
      (node (ref "U1") (pin "83") (pinfunction "VSS_83") (pintype "power_in"))
      (node (ref "U1") (pin "94") (pinfunction "VSS_94") (pintype "power_in"))
      (node (ref "Y1") (pin "2") (pinfunction "GND_1_2") (pintype "passive"))
      (node (ref "Y1") (pin "4") (pinfunction "GND_2_4") (pintype "passive"))
    )
    (net (code "123") (name "Net-(R154-Pad1)") (class "Default")
      (node (ref "R154") (pin "1") (pinfunction "1_1") (pintype "passive"))
      (node (ref "R156") (pin "1") (pinfunction "1_1") (pintype "passive"))
    )
    (net (code "124") (name "Net-(R155-Pad1)") (class "Default")
      (node (ref "R155") (pin "1") (pinfunction "1_1") (pintype "passive"))
      (node (ref "R158") (pin "1") (pinfunction "1_1") (pintype "passive"))
    )
    (net (code "125") (name "Net-(R205-Pad1)") (class "Default")
      (node (ref "R205") (pin "1") (pinfunction "1_1") (pintype "passive"))
      (node (ref "R207") (pin "1") (pinfunction "1_1") (pintype "passive"))
    )
    (net (code "126") (name "Net-(R206-Pad1)") (class "Default")
      (node (ref "R206") (pin "1") (pinfunction "1_1") (pintype "passive"))
      (node (ref "R208") (pin "1") (pinfunction "1_1") (pintype "passive"))
    )
    (net (code "127") (name "VDD") (class "Default")
      (node (ref "C1") (pin "1") (pinfunction "1_1") (pintype "passive"))
      (node (ref "C10") (pin "2") (pinfunction "2_2") (pintype "passive"))
      (node (ref "C11") (pin "2") (pinfunction "2_2") (pintype "passive"))
      (node (ref "C12") (pin "2") (pinfunction "2_2") (pintype "passive"))
      (node (ref "C13") (pin "2") (pinfunction "2_2") (pintype "passive"))
      (node (ref "C14") (pin "2") (pinfunction "2_2") (pintype "passive"))
      (node (ref "C15") (pin "2") (pinfunction "2_2") (pintype "passive"))
      (node (ref "C16") (pin "2") (pinfunction "2_2") (pintype "passive"))
      (node (ref "C17") (pin "2") (pinfunction "2_2") (pintype "passive"))
      (node (ref "C2") (pin "1") (pinfunction "1_1") (pintype "passive"))
      (node (ref "C20") (pin "2") (pinfunction "2_2") (pintype "passive"))
      (node (ref "C3") (pin "2") (pinfunction "2_2") (pintype "passive"))
      (node (ref "C4") (pin "2") (pinfunction "2_2") (pintype "passive"))
      (node (ref "C5") (pin "2") (pinfunction "2_2") (pintype "passive"))
      (node (ref "C6") (pin "2") (pinfunction "2_2") (pintype "passive"))
      (node (ref "C7") (pin "2") (pinfunction "2_2") (pintype "passive"))
      (node (ref "C8") (pin "2") (pinfunction "2_2") (pintype "passive"))
      (node (ref "C9") (pin "2") (pinfunction "2_2") (pintype "passive"))
      (node (ref "FB1") (pin "2") (pinfunction "2_2") (pintype "passive"))
      (node (ref "R2") (pin "2") (pinfunction "2_2") (pintype "passive"))
      (node (ref "SW1") (pin "1") (pinfunction "1_1") (pintype "passive"))
      (node (ref "U1") (pin "108") (pinfunction "VDD_108") (pintype "power_in"))
      (node (ref "U1") (pin "121") (pinfunction "VDD_121") (pintype "power_in"))
      (node (ref "U1") (pin "131") (pinfunction "VDD_131") (pintype "power_in"))
      (node (ref "U1") (pin "143") (pinfunction "PDR_ON_143") (pintype "input"))
      (node (ref "U1") (pin "144") (pinfunction "VDD_144") (pintype "power_in"))
      (node (ref "U1") (pin "17") (pinfunction "VDD_17") (pintype "power_in"))
      (node (ref "U1") (pin "30") (pinfunction "VDD_30") (pintype "power_in"))
      (node (ref "U1") (pin "39") (pinfunction "VDD_39") (pintype "power_in"))
      (node (ref "U1") (pin "52") (pinfunction "VDD_52") (pintype "power_in"))
      (node (ref "U1") (pin "6") (pinfunction "VBAT_6") (pintype "power_in"))
      (node (ref "U1") (pin "62") (pinfunction "VDD_62") (pintype "power_in"))
      (node (ref "U1") (pin "72") (pinfunction "VDD_72") (pintype "power_in"))
      (node (ref "U1") (pin "84") (pinfunction "VDD_84") (pintype "power_in"))
      (node (ref "U1") (pin "95") (pinfunction "VDDUSB_95") (pintype "power_in"))
    )
    (net (code "128") (name "unconnected-(R193-Pad1)") (class "Default")
      (node (ref "R193") (pin "1") (pinfunction "1_1") (pintype "passive"))
    )
    (net (code "129") (name "unconnected-(R198-Pad1)") (class "Default")
      (node (ref "R198") (pin "1") (pinfunction "1_1") (pintype "passive"))
    )
    (net (code "130") (name "unconnected-(R199-Pad1)") (class "Default")
      (node (ref "R199") (pin "1") (pinfunction "1_1") (pintype "passive"))
    )
    (net (code "131") (name "unconnected-(R200-Pad1)") (class "Default")
      (node (ref "R200") (pin "1") (pinfunction "1_1") (pintype "passive"))
    )
    (net (code "132") (name "unconnected-(R201-Pad1)") (class "Default")
      (node (ref "R201") (pin "1") (pinfunction "1_1") (pintype "passive"))
    )
    (net (code "133") (name "unconnected-(R202-Pad1)") (class "Default")
      (node (ref "R202") (pin "1") (pinfunction "1_1") (pintype "passive"))
    )
    (net (code "134") (name "unconnected-(R203-Pad1)") (class "Default")
      (node (ref "R203") (pin "1") (pinfunction "1_1") (pintype "passive"))
    )
    (net (code "135") (name "unconnected-(R204-Pad1)") (class "Default")
      (node (ref "R204") (pin "1") (pinfunction "1_1") (pintype "passive"))
    )
    (net (code "136") (name "unconnected-(U1A-PA9-Pad101)") (class "Default")
      (node (ref "U1") (pin "101") (pinfunction "PA9_101") (pintype "bidirectional+no_connect"))
    )
    (net (code "137") (name "unconnected-(U1A-PA10-Pad102)") (class "Default")
      (node (ref "U1") (pin "102") (pinfunction "PA10_102") (pintype "bidirectional+no_connect"))
    )
    (net (code "138") (name "unconnected-(U1A-PA15(JTDI)-Pad110)") (class "Default")
      (node (ref "U1") (pin "110") (pinfunction "PA15(JTDI)_110") (pintype "bidirectional"))
    )
    (net (code "139") (name "unconnected-(U1A-PB1-Pad47)") (class "Default")
      (node (ref "U1") (pin "47") (pinfunction "PB1_47") (pintype "bidirectional+no_connect"))
    )
    (net (code "140") (name "unconnected-(U1A-PB14-Pad75)") (class "Default")
      (node (ref "U1") (pin "75") (pinfunction "PB14_75") (pintype "bidirectional+no_connect"))
    )
    (net (code "141") (name "unconnected-(U1A-PC8-Pad98)") (class "Default")
      (node (ref "U1") (pin "98") (pinfunction "PC8_98") (pintype "bidirectional+no_connect"))
    )
    (net (code "142") (name "unconnected-(U1A-PC12-Pad113)") (class "Default")
      (node (ref "U1") (pin "113") (pinfunction "PC12_113") (pintype "bidirectional+no_connect"))
    )
    (net (code "143") (name "unconnected-(U1A-PD4-Pad118)") (class "Default")
      (node (ref "U1") (pin "118") (pinfunction "PD4_118") (pintype "bidirectional"))
    )
    (net (code "144") (name "unconnected-(U1A-PD7-Pad123)") (class "Default")
      (node (ref "U1") (pin "123") (pinfunction "PD7_123") (pintype "bidirectional+no_connect"))
    )
    (net (code "145") (name "unconnected-(U1A-PE7-Pad58)") (class "Default")
      (node (ref "U1") (pin "58") (pinfunction "PE7_58") (pintype "bidirectional+no_connect"))
    )
    (net (code "146") (name "unconnected-(U1A-PE8-Pad59)") (class "Default")
      (node (ref "U1") (pin "59") (pinfunction "PE8_59") (pintype "bidirectional+no_connect"))
    )
    (net (code "147") (name "unconnected-(U1A-PE9-Pad60)") (class "Default")
      (node (ref "U1") (pin "60") (pinfunction "PE9_60") (pintype "bidirectional+no_connect"))
    )
    (net (code "148") (name "unconnected-(U1A-PE10-Pad63)") (class "Default")
      (node (ref "U1") (pin "63") (pinfunction "PE10_63") (pintype "bidirectional+no_connect"))
    )
    (net (code "149") (name "unconnected-(U1A-PE13-Pad66)") (class "Default")
      (node (ref "U1") (pin "66") (pinfunction "PE13_66") (pintype "bidirectional+no_connect"))
    )
    (net (code "150") (name "unconnected-(U1A-PE15-Pad68)") (class "Default")
      (node (ref "U1") (pin "68") (pinfunction "PE15_68") (pintype "bidirectional+no_connect"))
    )
    (net (code "151") (name "unconnected-(U1A-PF1-Pad11)") (class "Default")
      (node (ref "U1") (pin "11") (pinfunction "PF1_11") (pintype "bidirectional+no_connect"))
    )
    (net (code "152") (name "unconnected-(U1A-PF2-Pad12)") (class "Default")
      (node (ref "U1") (pin "12") (pinfunction "PF2_12") (pintype "bidirectional+no_connect"))
    )
    (net (code "153") (name "unconnected-(U1A-PF10-Pad22)") (class "Default")
      (node (ref "U1") (pin "22") (pinfunction "PF10_22") (pintype "bidirectional+no_connect"))
    )
    (net (code "154") (name "unconnected-(U1A-PF11-Pad49)") (class "Default")
      (node (ref "U1") (pin "49") (pinfunction "PF11_49") (pintype "bidirectional+no_connect"))
    )
    (net (code "155") (name "unconnected-(U1A-PF12-Pad50)") (class "Default")
      (node (ref "U1") (pin "50") (pinfunction "PF12_50") (pintype "bidirectional+no_connect"))
    )
    (net (code "156") (name "unconnected-(U1A-PF13-Pad53)") (class "Default")
      (node (ref "U1") (pin "53") (pinfunction "PF13_53") (pintype "bidirectional+no_connect"))
    )
    (net (code "157") (name "unconnected-(U1A-PF14-Pad54)") (class "Default")
      (node (ref "U1") (pin "54") (pinfunction "PF14_54") (pintype "bidirectional+no_connect"))
    )
    (net (code "158") (name "unconnected-(U1A-PF15-Pad55)") (class "Default")
      (node (ref "U1") (pin "55") (pinfunction "PF15_55") (pintype "bidirectional+no_connect"))
    )
    (net (code "159") (name "unconnected-(U1B-PG0-Pad56)") (class "Default")
      (node (ref "U1") (pin "56") (pinfunction "PG0_56") (pintype "bidirectional+no_connect"))
    )
    (net (code "160") (name "unconnected-(U1B-PG1-Pad57)") (class "Default")
      (node (ref "U1") (pin "57") (pinfunction "PG1_57") (pintype "bidirectional+no_connect"))
    )
    (net (code "161") (name "unconnected-(U1B-PG13-Pad128)") (class "Default")
      (node (ref "U1") (pin "128") (pinfunction "PG13_128") (pintype "bidirectional+no_connect"))
    )
    (net (code "162") (name "unconnected-(U1B-PG14-Pad129)") (class "Default")
      (node (ref "U1") (pin "129") (pinfunction "PG14_129") (pintype "bidirectional+no_connect"))
    )
    (net (code "163") (name "unconnected-(U1B-PG15-Pad132)") (class "Default")
      (node (ref "U1") (pin "132") (pinfunction "PG15_132") (pintype "bidirectional+no_connect"))
    )
  )
)
